# TMS320F28379D.net
KiCad netlist of a schematic drawn in Altium Designer
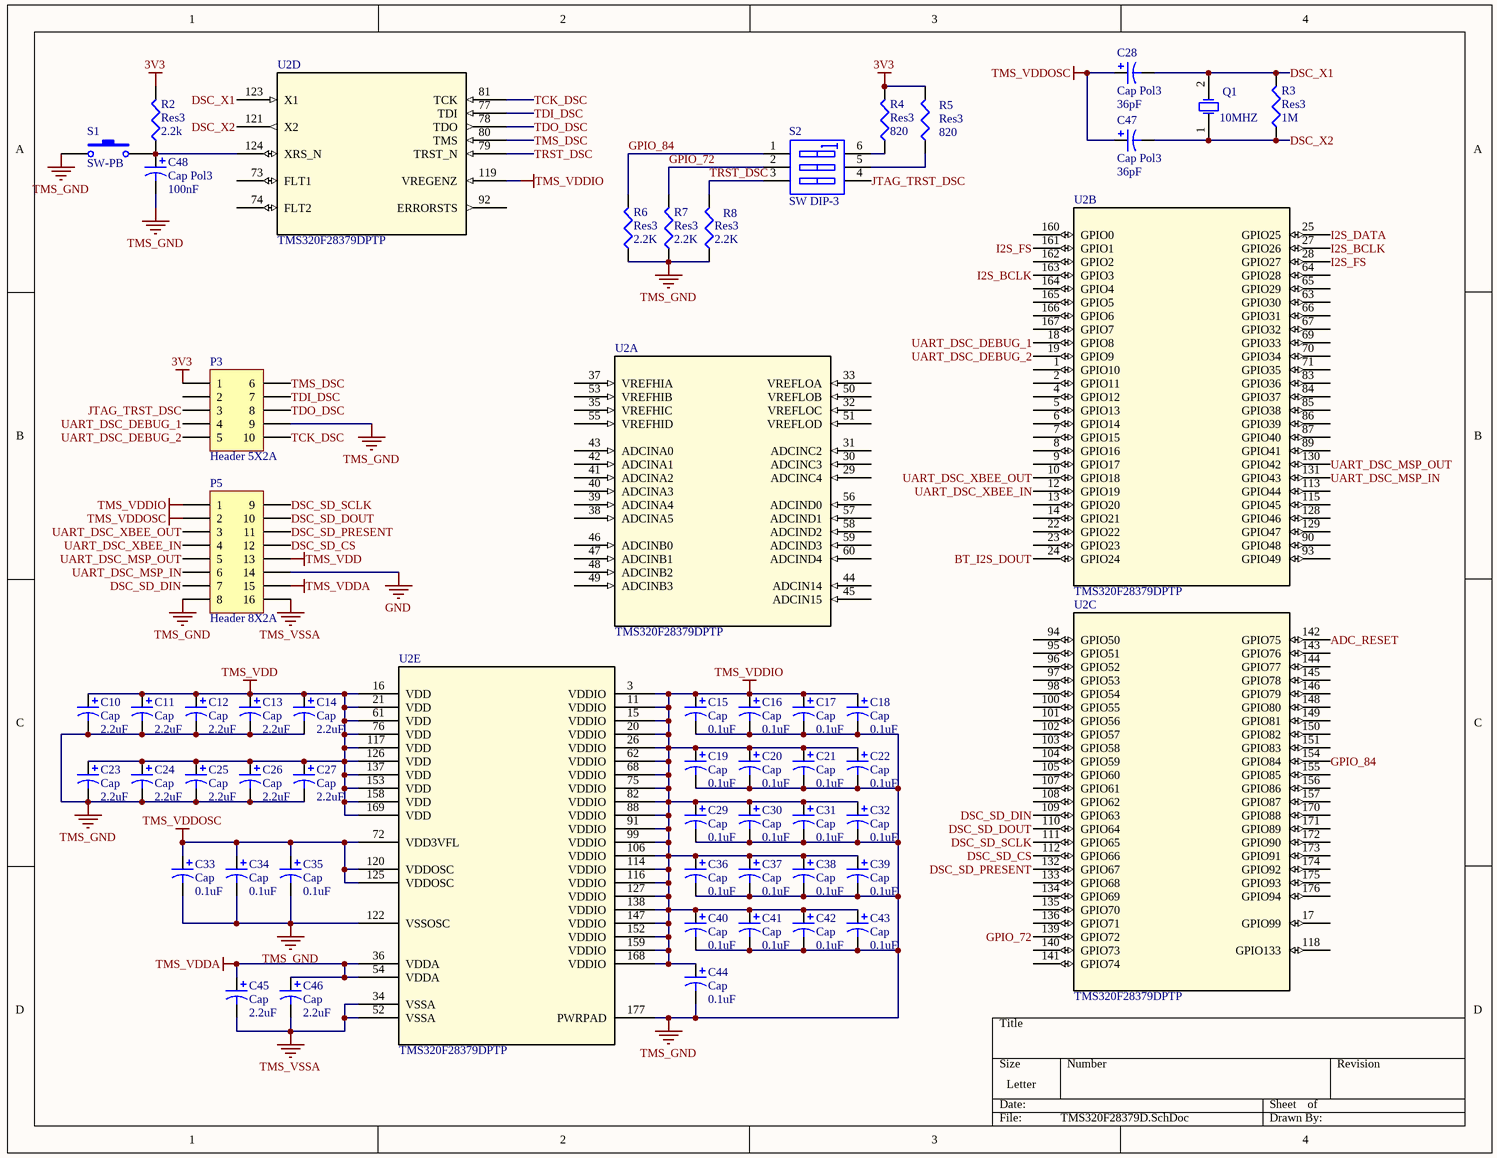
[diagram p0: TMS320F28379D.SchDoc]

(export (version "E")
  (design (tool "Eeschema 10.0.6"))
  (components
    (comp (ref "C10")
      (value "Cap")
      (footprint "C0805")
      (description "Polarized Capacitor (Surface Mount)")
      (fields (field (name "ALTIUM_VALUE") "2.2uF") (field (name "PUBLISHER") "Altium Limited"))
      (libsource (lib "Miscellaneous Devices") (part "Cap Pol3"))
    )
    (comp (ref "C11")
      (value "Cap")
      (footprint "C0805")
      (description "Polarized Capacitor (Surface Mount)")
      (fields (field (name "ALTIUM_VALUE") "2.2uF") (field (name "PUBLISHER") "Altium Limited"))
      (libsource (lib "Miscellaneous Devices") (part "Cap Pol3"))
    )
    (comp (ref "C12")
      (value "Cap")
      (footprint "C0805")
      (description "Polarized Capacitor (Surface Mount)")
      (fields (field (name "ALTIUM_VALUE") "2.2uF") (field (name "PUBLISHER") "Altium Limited"))
      (libsource (lib "Miscellaneous Devices") (part "Cap Pol3"))
    )
    (comp (ref "C13")
      (value "Cap")
      (footprint "C0805")
      (description "Polarized Capacitor (Surface Mount)")
      (fields (field (name "ALTIUM_VALUE") "2.2uF") (field (name "PUBLISHER") "Altium Limited"))
      (libsource (lib "Miscellaneous Devices") (part "Cap Pol3"))
    )
    (comp (ref "C14")
      (value "Cap")
      (footprint "C0805")
      (description "Polarized Capacitor (Surface Mount)")
      (fields (field (name "ALTIUM_VALUE") "2.2uF") (field (name "PUBLISHER") "Altium Limited"))
      (libsource (lib "Miscellaneous Devices") (part "Cap Pol3"))
    )
    (comp (ref "C15")
      (value "Cap")
      (footprint "C0805")
      (description "Polarized Capacitor (Surface Mount)")
      (fields (field (name "ALTIUM_VALUE") "0.1uF") (field (name "PUBLISHER") "Altium Limited"))
      (libsource (lib "Miscellaneous Devices") (part "Cap Pol3"))
    )
    (comp (ref "C16")
      (value "Cap")
      (footprint "C0805")
      (description "Polarized Capacitor (Surface Mount)")
      (fields (field (name "ALTIUM_VALUE") "0.1uF") (field (name "PUBLISHER") "Altium Limited"))
      (libsource (lib "Miscellaneous Devices") (part "Cap Pol3"))
    )
    (comp (ref "C17")
      (value "Cap")
      (footprint "C0805")
      (description "Polarized Capacitor (Surface Mount)")
      (fields (field (name "ALTIUM_VALUE") "0.1uF") (field (name "PUBLISHER") "Altium Limited"))
      (libsource (lib "Miscellaneous Devices") (part "Cap Pol3"))
    )
    (comp (ref "C18")
      (value "Cap")
      (footprint "C0805")
      (description "Polarized Capacitor (Surface Mount)")
      (fields (field (name "ALTIUM_VALUE") "0.1uF") (field (name "PUBLISHER") "Altium Limited"))
      (libsource (lib "Miscellaneous Devices") (part "Cap Pol3"))
    )
    (comp (ref "C19")
      (value "Cap")
      (footprint "C0805")
      (description "Polarized Capacitor (Surface Mount)")
      (fields (field (name "ALTIUM_VALUE") "0.1uF") (field (name "PUBLISHER") "Altium Limited"))
      (libsource (lib "Miscellaneous Devices") (part "Cap Pol3"))
    )
    (comp (ref "C20")
      (value "Cap")
      (footprint "C0805")
      (description "Polarized Capacitor (Surface Mount)")
      (fields (field (name "ALTIUM_VALUE") "0.1uF") (field (name "PUBLISHER") "Altium Limited"))
      (libsource (lib "Miscellaneous Devices") (part "Cap Pol3"))
    )
    (comp (ref "C21")
      (value "Cap")
      (footprint "C0805")
      (description "Polarized Capacitor (Surface Mount)")
      (fields (field (name "ALTIUM_VALUE") "0.1uF") (field (name "PUBLISHER") "Altium Limited"))
      (libsource (lib "Miscellaneous Devices") (part "Cap Pol3"))
    )
    (comp (ref "C22")
      (value "Cap")
      (footprint "C0805")
      (description "Polarized Capacitor (Surface Mount)")
      (fields (field (name "ALTIUM_VALUE") "0.1uF") (field (name "PUBLISHER") "Altium Limited"))
      (libsource (lib "Miscellaneous Devices") (part "Cap Pol3"))
    )
    (comp (ref "C23")
      (value "Cap")
      (footprint "C0805")
      (description "Polarized Capacitor (Surface Mount)")
      (fields (field (name "ALTIUM_VALUE") "2.2uF") (field (name "PUBLISHER") "Altium Limited"))
      (libsource (lib "Miscellaneous Devices") (part "Cap Pol3"))
    )
    (comp (ref "C24")
      (value "Cap")
      (footprint "C0805")
      (description "Polarized Capacitor (Surface Mount)")
      (fields (field (name "ALTIUM_VALUE") "2.2uF") (field (name "PUBLISHER") "Altium Limited"))
      (libsource (lib "Miscellaneous Devices") (part "Cap Pol3"))
    )
    (comp (ref "C25")
      (value "Cap")
      (footprint "C0805")
      (description "Polarized Capacitor (Surface Mount)")
      (fields (field (name "ALTIUM_VALUE") "2.2uF") (field (name "PUBLISHER") "Altium Limited"))
      (libsource (lib "Miscellaneous Devices") (part "Cap Pol3"))
    )
    (comp (ref "C26")
      (value "Cap")
      (footprint "C0805")
      (description "Polarized Capacitor (Surface Mount)")
      (fields (field (name "ALTIUM_VALUE") "2.2uF") (field (name "PUBLISHER") "Altium Limited"))
      (libsource (lib "Miscellaneous Devices") (part "Cap Pol3"))
    )
    (comp (ref "C27")
      (value "Cap")
      (footprint "C0805")
      (description "Polarized Capacitor (Surface Mount)")
      (fields (field (name "ALTIUM_VALUE") "2.2uF") (field (name "PUBLISHER") "Altium Limited"))
      (libsource (lib "Miscellaneous Devices") (part "Cap Pol3"))
    )
    (comp (ref "C28")
      (value "Cap Pol3")
      (footprint "C0805")
      (description "Polarized Capacitor (Surface Mount)")
      (fields (field (name "ALTIUM_VALUE") "36pF") (field (name "PUBLISHER") "Altium Limited"))
      (libsource (lib "Miscellaneous Devices") (part "Cap Pol3"))
    )
    (comp (ref "C29")
      (value "Cap")
      (footprint "C0805")
      (description "Polarized Capacitor (Surface Mount)")
      (fields (field (name "ALTIUM_VALUE") "0.1uF") (field (name "PUBLISHER") "Altium Limited"))
      (libsource (lib "Miscellaneous Devices") (part "Cap Pol3"))
    )
    (comp (ref "C30")
      (value "Cap")
      (footprint "C0805")
      (description "Polarized Capacitor (Surface Mount)")
      (fields (field (name "ALTIUM_VALUE") "0.1uF") (field (name "PUBLISHER") "Altium Limited"))
      (libsource (lib "Miscellaneous Devices") (part "Cap Pol3"))
    )
    (comp (ref "C31")
      (value "Cap")
      (footprint "C0805")
      (description "Polarized Capacitor (Surface Mount)")
      (fields (field (name "ALTIUM_VALUE") "0.1uF") (field (name "PUBLISHER") "Altium Limited"))
      (libsource (lib "Miscellaneous Devices") (part "Cap Pol3"))
    )
    (comp (ref "C32")
      (value "Cap")
      (footprint "C0805")
      (description "Polarized Capacitor (Surface Mount)")
      (fields (field (name "ALTIUM_VALUE") "0.1uF") (field (name "PUBLISHER") "Altium Limited"))
      (libsource (lib "Miscellaneous Devices") (part "Cap Pol3"))
    )
    (comp (ref "C33")
      (value "Cap")
      (footprint "C0805")
      (description "Polarized Capacitor (Surface Mount)")
      (fields (field (name "ALTIUM_VALUE") "0.1uF") (field (name "PUBLISHER") "Altium Limited"))
      (libsource (lib "Miscellaneous Devices") (part "Cap Pol3"))
    )
    (comp (ref "C34")
      (value "Cap")
      (footprint "C0805")
      (description "Polarized Capacitor (Surface Mount)")
      (fields (field (name "ALTIUM_VALUE") "0.1uF") (field (name "PUBLISHER") "Altium Limited"))
      (libsource (lib "Miscellaneous Devices") (part "Cap Pol3"))
    )
    (comp (ref "C35")
      (value "Cap")
      (footprint "C0805")
      (description "Polarized Capacitor (Surface Mount)")
      (fields (field (name "ALTIUM_VALUE") "0.1uF") (field (name "PUBLISHER") "Altium Limited"))
      (libsource (lib "Miscellaneous Devices") (part "Cap Pol3"))
    )
    (comp (ref "C36")
      (value "Cap")
      (footprint "C0805")
      (description "Polarized Capacitor (Surface Mount)")
      (fields (field (name "ALTIUM_VALUE") "0.1uF") (field (name "PUBLISHER") "Altium Limited"))
      (libsource (lib "Miscellaneous Devices") (part "Cap Pol3"))
    )
    (comp (ref "C37")
      (value "Cap")
      (footprint "C0805")
      (description "Polarized Capacitor (Surface Mount)")
      (fields (field (name "ALTIUM_VALUE") "0.1uF") (field (name "PUBLISHER") "Altium Limited"))
      (libsource (lib "Miscellaneous Devices") (part "Cap Pol3"))
    )
    (comp (ref "C38")
      (value "Cap")
      (footprint "C0805")
      (description "Polarized Capacitor (Surface Mount)")
      (fields (field (name "ALTIUM_VALUE") "0.1uF") (field (name "PUBLISHER") "Altium Limited"))
      (libsource (lib "Miscellaneous Devices") (part "Cap Pol3"))
    )
    (comp (ref "C39")
      (value "Cap")
      (footprint "C0805")
      (description "Polarized Capacitor (Surface Mount)")
      (fields (field (name "ALTIUM_VALUE") "0.1uF") (field (name "PUBLISHER") "Altium Limited"))
      (libsource (lib "Miscellaneous Devices") (part "Cap Pol3"))
    )
    (comp (ref "C40")
      (value "Cap")
      (footprint "C0805")
      (description "Polarized Capacitor (Surface Mount)")
      (fields (field (name "ALTIUM_VALUE") "0.1uF") (field (name "PUBLISHER") "Altium Limited"))
      (libsource (lib "Miscellaneous Devices") (part "Cap Pol3"))
    )
    (comp (ref "C41")
      (value "Cap")
      (footprint "C0805")
      (description "Polarized Capacitor (Surface Mount)")
      (fields (field (name "ALTIUM_VALUE") "0.1uF") (field (name "PUBLISHER") "Altium Limited"))
      (libsource (lib "Miscellaneous Devices") (part "Cap Pol3"))
    )
    (comp (ref "C42")
      (value "Cap")
      (footprint "C0805")
      (description "Polarized Capacitor (Surface Mount)")
      (fields (field (name "ALTIUM_VALUE") "0.1uF") (field (name "PUBLISHER") "Altium Limited"))
      (libsource (lib "Miscellaneous Devices") (part "Cap Pol3"))
    )
    (comp (ref "C43")
      (value "Cap")
      (footprint "C0805")
      (description "Polarized Capacitor (Surface Mount)")
      (fields (field (name "ALTIUM_VALUE") "0.1uF") (field (name "PUBLISHER") "Altium Limited"))
      (libsource (lib "Miscellaneous Devices") (part "Cap Pol3"))
    )
    (comp (ref "C44")
      (value "Cap")
      (footprint "C0805")
      (description "Polarized Capacitor (Surface Mount)")
      (fields (field (name "ALTIUM_VALUE") "0.1uF") (field (name "PUBLISHER") "Altium Limited"))
      (libsource (lib "Miscellaneous Devices") (part "Cap Pol3"))
    )
    (comp (ref "C45")
      (value "Cap")
      (footprint "C0805")
      (description "Polarized Capacitor (Surface Mount)")
      (fields (field (name "ALTIUM_VALUE") "2.2uF") (field (name "PUBLISHER") "Altium Limited"))
      (libsource (lib "Miscellaneous Devices") (part "Cap Pol3"))
    )
    (comp (ref "C46")
      (value "Cap")
      (footprint "C0805")
      (description "Polarized Capacitor (Surface Mount)")
      (fields (field (name "ALTIUM_VALUE") "2.2uF") (field (name "PUBLISHER") "Altium Limited"))
      (libsource (lib "Miscellaneous Devices") (part "Cap Pol3"))
    )
    (comp (ref "C47")
      (value "Cap Pol3")
      (footprint "C0805")
      (description "Polarized Capacitor (Surface Mount)")
      (fields (field (name "ALTIUM_VALUE") "36pF") (field (name "PUBLISHER") "Altium Limited"))
      (libsource (lib "Miscellaneous Devices") (part "Cap Pol3"))
    )
    (comp (ref "C48")
      (value "Cap Pol3")
      (footprint "C0805")
      (description "Polarized Capacitor (Surface Mount)")
      (fields (field (name "ALTIUM_VALUE") "100nF") (field (name "PUBLISHER") "Altium Limited"))
      (libsource (lib "Miscellaneous Devices") (part "Cap Pol3"))
    )
    (comp (ref "P3")
      (value "Header 5X2A")
      (footprint "HDR2X5_CEN")
      (description "Header, 5-Pin, Dual row")
      (fields (field (name "PUBLISHER") "Altium Limited"))
      (libsource (lib "Miscellaneous Connectors") (part "Header 5X2A"))
    )
    (comp (ref "P5")
      (value "Header 8X2A")
      (footprint "HDR2X8_CEN")
      (description "Header, 8-Pin, Dual row")
      (fields (field (name "PUBLISHER") "Altium Limited"))
      (libsource (lib "Miscellaneous Connectors") (part "Header 8X2A"))
    )
    (comp (ref "Q1")
      (value "10MHZ")
      (footprint "HC-49U")
      (description "Crystal Oscillator")
      (fields (field (name "PUBLISHER") "Altium Limited"))
      (libsource (lib "ECS Crystal Oscillator") (part "ECS-10-13-1"))
    )
    (comp (ref "R2")
      (value "Res3")
      (footprint "14-1210")
      (description "Resistor")
      (fields (field (name "ALTIUM_VALUE") "2.2k") (field (name "PUBLISHER") "Altium Limited"))
      (libsource (lib "Miscellaneous Devices") (part "Res3"))
    )
    (comp (ref "R3")
      (value "Res3")
      (footprint "14-1210")
      (description "Resistor")
      (fields (field (name "ALTIUM_VALUE") "1M") (field (name "PUBLISHER") "Altium Limited"))
      (libsource (lib "Miscellaneous Devices") (part "Res3"))
    )
    (comp (ref "R4")
      (value "Res3")
      (footprint "14-1210")
      (description "Resistor")
      (fields (field (name "ALTIUM_VALUE") "820") (field (name "PUBLISHER") "Altium Limited"))
      (libsource (lib "Miscellaneous Devices") (part "Res3"))
    )
    (comp (ref "R5")
      (value "Res3")
      (footprint "14-1210")
      (description "Resistor")
      (fields (field (name "ALTIUM_VALUE") "820") (field (name "PUBLISHER") "Altium Limited"))
      (libsource (lib "Miscellaneous Devices") (part "Res3"))
    )
    (comp (ref "R6")
      (value "Res3")
      (footprint "14-1210")
      (description "Resistor")
      (fields (field (name "ALTIUM_VALUE") "2.2K") (field (name "PUBLISHER") "Altium Limited"))
      (libsource (lib "Miscellaneous Devices") (part "Res3"))
    )
    (comp (ref "R7")
      (value "Res3")
      (footprint "14-1210")
      (description "Resistor")
      (fields (field (name "ALTIUM_VALUE") "2.2K") (field (name "PUBLISHER") "Altium Limited"))
      (libsource (lib "Miscellaneous Devices") (part "Res3"))
    )
    (comp (ref "R8")
      (value "Res3")
      (footprint "14-1210")
      (description "Resistor")
      (fields (field (name "ALTIUM_VALUE") "2.2K") (field (name "PUBLISHER") "Altium Limited"))
      (libsource (lib "Miscellaneous Devices") (part "Res3"))
    )
    (comp (ref "S1")
      (value "SW-PB")
      (footprint "SW PB")
      (description "DIGIKEY SW400-ND")
      (fields (field (name "PUBLISHER") "Altium Limited"))
      (libsource (lib "ECE LIB new") (part "SW-PB_2"))
    )
    (comp (ref "S2")
      (value "SW DIP-3")
      (footprint "DIP-6")
      (description "DIP Switch, 3 Position, SPST")
      (fields (field (name "PUBLISHER") "Altium Limited"))
      (libsource (lib "Miscellaneous Devices") (part "SW DIP-3"))
    )
    (comp (ref "U2")
      (value "TMS320F28379DPTP")
      (footprint "PTP0176F_N")
      (description "Imported")
      (fields
        (field (name "PARTNUMBER") "TMS320F28379DPTPS")
        (field (name "MANUFACTURER") "Texas Instruments")
      )
      (libsource (lib "TMS320F28379DPTP") (part "TMS320F28379DPTP"))
    )
  )
  (nets
    (net (code "1") (name "/ADC_RESET") (class "Default")
      (node (ref "U2") (pin "142") (pinfunction "GPIO75_142") (pintype "bidirectional"))
    )
    (net (code "2") (name "/BT_I2S_DOUT") (class "Default")
      (node (ref "U2") (pin "24") (pinfunction "GPIO24_24") (pintype "bidirectional"))
    )
    (net (code "3") (name "/DSC_SD_CS") (class "Default")
      (node (ref "P5") (pin "12") (pinfunction "12_12") (pintype "passive"))
      (node (ref "U2") (pin "112") (pinfunction "GPIO66_112") (pintype "bidirectional"))
    )
    (net (code "4") (name "/DSC_SD_DIN") (class "Default")
      (node (ref "P5") (pin "7") (pinfunction "7_7") (pintype "passive"))
      (node (ref "U2") (pin "109") (pinfunction "GPIO63_109") (pintype "bidirectional"))
    )
    (net (code "5") (name "/DSC_SD_DOUT") (class "Default")
      (node (ref "P5") (pin "10") (pinfunction "10_10") (pintype "passive"))
      (node (ref "U2") (pin "110") (pinfunction "GPIO64_110") (pintype "bidirectional"))
    )
    (net (code "6") (name "/DSC_SD_PRESENT") (class "Default")
      (node (ref "P5") (pin "11") (pinfunction "11_11") (pintype "passive"))
      (node (ref "U2") (pin "132") (pinfunction "GPIO67_132") (pintype "bidirectional"))
    )
    (net (code "7") (name "/DSC_SD_SCLK") (class "Default")
      (node (ref "P5") (pin "9") (pinfunction "9_9") (pintype "passive"))
      (node (ref "U2") (pin "111") (pinfunction "GPIO65_111") (pintype "bidirectional"))
    )
    (net (code "8") (name "/DSC_X1") (class "Default")
      (node (ref "C28") (pin "2") (pinfunction "2_2") (pintype "passive"))
      (node (ref "Q1") (pin "2") (pinfunction "OSC2_2") (pintype "passive"))
      (node (ref "R3") (pin "2") (pinfunction "2_2") (pintype "passive"))
      (node (ref "U2") (pin "123") (pinfunction "X1_123") (pintype "input"))
    )
    (net (code "9") (name "/DSC_X2") (class "Default")
      (node (ref "C47") (pin "2") (pinfunction "2_2") (pintype "passive"))
      (node (ref "Q1") (pin "1") (pinfunction "OSC1_1") (pintype "passive"))
      (node (ref "R3") (pin "1") (pinfunction "1_1") (pintype "passive"))
      (node (ref "U2") (pin "121") (pinfunction "X2_121") (pintype "output"))
    )
    (net (code "10") (name "/GPIO_72") (class "Default")
      (node (ref "R7") (pin "2") (pinfunction "2_2") (pintype "passive"))
      (node (ref "S2") (pin "2") (pinfunction "A2_2") (pintype "passive"))
      (node (ref "U2") (pin "139") (pinfunction "GPIO72_139") (pintype "bidirectional"))
    )
    (net (code "11") (name "/GPIO_84") (class "Default")
      (node (ref "R6") (pin "2") (pinfunction "2_2") (pintype "passive"))
      (node (ref "S2") (pin "1") (pinfunction "A1_1") (pintype "passive"))
      (node (ref "U2") (pin "154") (pinfunction "GPIO84_154") (pintype "bidirectional"))
    )
    (net (code "12") (name "/I2S_BCLK") (class "Default")
      (node (ref "U2") (pin "163") (pinfunction "GPIO3_163") (pintype "bidirectional"))
      (node (ref "U2") (pin "27") (pinfunction "GPIO26_27") (pintype "bidirectional"))
    )
    (net (code "13") (name "/I2S_DATA") (class "Default")
      (node (ref "U2") (pin "25") (pinfunction "GPIO25_25") (pintype "bidirectional"))
    )
    (net (code "14") (name "/I2S_FS") (class "Default")
      (node (ref "U2") (pin "161") (pinfunction "GPIO1_161") (pintype "bidirectional"))
      (node (ref "U2") (pin "28") (pinfunction "GPIO27_28") (pintype "bidirectional"))
    )
    (net (code "15") (name "/JTAG_TRST_DSC") (class "Default")
      (node (ref "P3") (pin "3") (pinfunction "3_3") (pintype "passive"))
      (node (ref "S2") (pin "4") (pinfunction "B3_4") (pintype "passive"))
    )
    (net (code "16") (name "/TCK_DSC") (class "Default")
      (node (ref "P3") (pin "10") (pinfunction "10_10") (pintype "passive"))
      (node (ref "U2") (pin "81") (pinfunction "TCK_81") (pintype "input"))
    )
    (net (code "17") (name "/TDI_DSC") (class "Default")
      (node (ref "P3") (pin "7") (pinfunction "7_7") (pintype "passive"))
      (node (ref "U2") (pin "77") (pinfunction "TDI_77") (pintype "input"))
    )
    (net (code "18") (name "/TDO_DSC") (class "Default")
      (node (ref "P3") (pin "8") (pinfunction "8_8") (pintype "passive"))
      (node (ref "U2") (pin "78") (pinfunction "TDO_78") (pintype "output"))
    )
    (net (code "19") (name "/TMS_DSC") (class "Default")
      (node (ref "P3") (pin "6") (pinfunction "6_6") (pintype "passive"))
      (node (ref "U2") (pin "80") (pinfunction "TMS_80") (pintype "input"))
    )
    (net (code "20") (name "/TRST_DSC") (class "Default")
      (node (ref "R8") (pin "2") (pinfunction "2_2") (pintype "passive"))
      (node (ref "S2") (pin "3") (pinfunction "A3_3") (pintype "passive"))
      (node (ref "U2") (pin "79") (pinfunction "TRST_N_79") (pintype "input"))
    )
    (net (code "21") (name "/UART_DSC_DEBUG_1") (class "Default")
      (node (ref "P3") (pin "4") (pinfunction "4_4") (pintype "passive"))
      (node (ref "U2") (pin "18") (pinfunction "GPIO8_18") (pintype "bidirectional"))
    )
    (net (code "22") (name "/UART_DSC_DEBUG_2") (class "Default")
      (node (ref "P3") (pin "5") (pinfunction "5_5") (pintype "passive"))
      (node (ref "U2") (pin "19") (pinfunction "GPIO9_19") (pintype "bidirectional"))
    )
    (net (code "23") (name "/UART_DSC_MSP_IN") (class "Default")
      (node (ref "P5") (pin "6") (pinfunction "6_6") (pintype "passive"))
      (node (ref "U2") (pin "131") (pinfunction "GPIO43_131") (pintype "bidirectional"))
    )
    (net (code "24") (name "/UART_DSC_MSP_OUT") (class "Default")
      (node (ref "P5") (pin "5") (pinfunction "5_5") (pintype "passive"))
      (node (ref "U2") (pin "130") (pinfunction "GPIO42_130") (pintype "bidirectional"))
    )
    (net (code "25") (name "/UART_DSC_XBEE_IN") (class "Default")
      (node (ref "P5") (pin "4") (pinfunction "4_4") (pintype "passive"))
      (node (ref "U2") (pin "12") (pinfunction "GPIO19_12") (pintype "bidirectional"))
    )
    (net (code "26") (name "/UART_DSC_XBEE_OUT") (class "Default")
      (node (ref "P5") (pin "3") (pinfunction "3_3") (pintype "passive"))
      (node (ref "U2") (pin "10") (pinfunction "GPIO18_10") (pintype "bidirectional"))
    )
    (net (code "27") (name "3V3") (class "Default")
      (node (ref "P3") (pin "1") (pinfunction "1_1") (pintype "passive"))
      (node (ref "R2") (pin "2") (pinfunction "2_2") (pintype "passive"))
      (node (ref "R4") (pin "2") (pinfunction "2_2") (pintype "passive"))
      (node (ref "R5") (pin "2") (pinfunction "2_2") (pintype "passive"))
    )
    (net (code "28") (name "GND") (class "Default")
      (node (ref "P5") (pin "14") (pinfunction "14_14") (pintype "passive"))
    )
    (net (code "29") (name "Net-(S2-B1)") (class "Default")
      (node (ref "R4") (pin "1") (pinfunction "1_1") (pintype "passive"))
      (node (ref "S2") (pin "6") (pinfunction "B1_6") (pintype "passive"))
    )
    (net (code "30") (name "Net-(S2-B2)") (class "Default")
      (node (ref "R5") (pin "1") (pinfunction "1_1") (pintype "passive"))
      (node (ref "S2") (pin "5") (pinfunction "B2_5") (pintype "passive"))
    )
    (net (code "31") (name "Net-(U2D-XRS_N)") (class "Default")
      (node (ref "C48") (pin "1") (pinfunction "1_1") (pintype "passive"))
      (node (ref "R2") (pin "1") (pinfunction "1_1") (pintype "passive"))
      (node (ref "S1") (pin "2") (pinfunction "2_2") (pintype "passive"))
      (node (ref "U2") (pin "124") (pinfunction "XRS_N_124") (pintype "bidirectional"))
    )
    (net (code "32") (name "TMS_GND") (class "Default")
      (node (ref "C10") (pin "2") (pinfunction "2_2") (pintype "passive"))
      (node (ref "C11") (pin "2") (pinfunction "2_2") (pintype "passive"))
      (node (ref "C12") (pin "2") (pinfunction "2_2") (pintype "passive"))
      (node (ref "C13") (pin "2") (pinfunction "2_2") (pintype "passive"))
      (node (ref "C14") (pin "2") (pinfunction "2_2") (pintype "passive"))
      (node (ref "C15") (pin "2") (pinfunction "2_2") (pintype "passive"))
      (node (ref "C16") (pin "2") (pinfunction "2_2") (pintype "passive"))
      (node (ref "C17") (pin "2") (pinfunction "2_2") (pintype "passive"))
      (node (ref "C18") (pin "2") (pinfunction "2_2") (pintype "passive"))
      (node (ref "C19") (pin "2") (pinfunction "2_2") (pintype "passive"))
      (node (ref "C20") (pin "2") (pinfunction "2_2") (pintype "passive"))
      (node (ref "C21") (pin "2") (pinfunction "2_2") (pintype "passive"))
      (node (ref "C22") (pin "2") (pinfunction "2_2") (pintype "passive"))
      (node (ref "C23") (pin "2") (pinfunction "2_2") (pintype "passive"))
      (node (ref "C24") (pin "2") (pinfunction "2_2") (pintype "passive"))
      (node (ref "C25") (pin "2") (pinfunction "2_2") (pintype "passive"))
      (node (ref "C26") (pin "2") (pinfunction "2_2") (pintype "passive"))
      (node (ref "C27") (pin "2") (pinfunction "2_2") (pintype "passive"))
      (node (ref "C29") (pin "2") (pinfunction "2_2") (pintype "passive"))
      (node (ref "C30") (pin "2") (pinfunction "2_2") (pintype "passive"))
      (node (ref "C31") (pin "2") (pinfunction "2_2") (pintype "passive"))
      (node (ref "C32") (pin "2") (pinfunction "2_2") (pintype "passive"))
      (node (ref "C33") (pin "2") (pinfunction "2_2") (pintype "passive"))
      (node (ref "C34") (pin "2") (pinfunction "2_2") (pintype "passive"))
      (node (ref "C35") (pin "2") (pinfunction "2_2") (pintype "passive"))
      (node (ref "C36") (pin "2") (pinfunction "2_2") (pintype "passive"))
      (node (ref "C37") (pin "2") (pinfunction "2_2") (pintype "passive"))
      (node (ref "C38") (pin "2") (pinfunction "2_2") (pintype "passive"))
      (node (ref "C39") (pin "2") (pinfunction "2_2") (pintype "passive"))
      (node (ref "C40") (pin "2") (pinfunction "2_2") (pintype "passive"))
      (node (ref "C41") (pin "2") (pinfunction "2_2") (pintype "passive"))
      (node (ref "C42") (pin "2") (pinfunction "2_2") (pintype "passive"))
      (node (ref "C43") (pin "2") (pinfunction "2_2") (pintype "passive"))
      (node (ref "C44") (pin "2") (pinfunction "2_2") (pintype "passive"))
      (node (ref "C48") (pin "2") (pinfunction "2_2") (pintype "passive"))
      (node (ref "P3") (pin "9") (pinfunction "9_9") (pintype "passive"))
      (node (ref "P5") (pin "8") (pinfunction "8_8") (pintype "passive"))
      (node (ref "R6") (pin "1") (pinfunction "1_1") (pintype "passive"))
      (node (ref "R7") (pin "1") (pinfunction "1_1") (pintype "passive"))
      (node (ref "R8") (pin "1") (pinfunction "1_1") (pintype "passive"))
      (node (ref "S1") (pin "1") (pinfunction "1_1") (pintype "passive"))
      (node (ref "U2") (pin "122") (pinfunction "VSSOSC_122") (pintype "power_in"))
      (node (ref "U2") (pin "177") (pinfunction "PWRPAD_177") (pintype "power_in"))
    )
    (net (code "33") (name "TMS_VDD") (class "Default")
      (node (ref "C10") (pin "1") (pinfunction "1_1") (pintype "passive"))
      (node (ref "C11") (pin "1") (pinfunction "1_1") (pintype "passive"))
      (node (ref "C12") (pin "1") (pinfunction "1_1") (pintype "passive"))
      (node (ref "C13") (pin "1") (pinfunction "1_1") (pintype "passive"))
      (node (ref "C14") (pin "1") (pinfunction "1_1") (pintype "passive"))
      (node (ref "C23") (pin "1") (pinfunction "1_1") (pintype "passive"))
      (node (ref "C24") (pin "1") (pinfunction "1_1") (pintype "passive"))
      (node (ref "C25") (pin "1") (pinfunction "1_1") (pintype "passive"))
      (node (ref "C26") (pin "1") (pinfunction "1_1") (pintype "passive"))
      (node (ref "C27") (pin "1") (pinfunction "1_1") (pintype "passive"))
      (node (ref "P5") (pin "13") (pinfunction "13_13") (pintype "passive"))
      (node (ref "U2") (pin "117") (pinfunction "VDD_117") (pintype "power_in"))
      (node (ref "U2") (pin "126") (pinfunction "VDD_126") (pintype "power_in"))
      (node (ref "U2") (pin "137") (pinfunction "VDD_137") (pintype "power_in"))
      (node (ref "U2") (pin "153") (pinfunction "VDD_153") (pintype "power_in"))
      (node (ref "U2") (pin "158") (pinfunction "VDD_158") (pintype "power_in"))
      (node (ref "U2") (pin "16") (pinfunction "VDD_16") (pintype "power_in"))
      (node (ref "U2") (pin "169") (pinfunction "VDD_169") (pintype "power_in"))
      (node (ref "U2") (pin "21") (pinfunction "VDD_21") (pintype "power_in"))
      (node (ref "U2") (pin "61") (pinfunction "VDD_61") (pintype "power_in"))
      (node (ref "U2") (pin "76") (pinfunction "VDD_76") (pintype "power_in"))
    )
    (net (code "34") (name "TMS_VDDA") (class "Default")
      (node (ref "C45") (pin "1") (pinfunction "1_1") (pintype "passive"))
      (node (ref "C46") (pin "1") (pinfunction "1_1") (pintype "passive"))
      (node (ref "P5") (pin "15") (pinfunction "15_15") (pintype "passive"))
      (node (ref "U2") (pin "36") (pinfunction "VDDA_36") (pintype "power_in"))
      (node (ref "U2") (pin "54") (pinfunction "VDDA_54") (pintype "power_in"))
    )
    (net (code "35") (name "TMS_VDDIO") (class "Default")
      (node (ref "C15") (pin "1") (pinfunction "1_1") (pintype "passive"))
      (node (ref "C16") (pin "1") (pinfunction "1_1") (pintype "passive"))
      (node (ref "C17") (pin "1") (pinfunction "1_1") (pintype "passive"))
      (node (ref "C18") (pin "1") (pinfunction "1_1") (pintype "passive"))
      (node (ref "C19") (pin "1") (pinfunction "1_1") (pintype "passive"))
      (node (ref "C20") (pin "1") (pinfunction "1_1") (pintype "passive"))
      (node (ref "C21") (pin "1") (pinfunction "1_1") (pintype "passive"))
      (node (ref "C22") (pin "1") (pinfunction "1_1") (pintype "passive"))
      (node (ref "C29") (pin "1") (pinfunction "1_1") (pintype "passive"))
      (node (ref "C30") (pin "1") (pinfunction "1_1") (pintype "passive"))
      (node (ref "C31") (pin "1") (pinfunction "1_1") (pintype "passive"))
      (node (ref "C32") (pin "1") (pinfunction "1_1") (pintype "passive"))
      (node (ref "C36") (pin "1") (pinfunction "1_1") (pintype "passive"))
      (node (ref "C37") (pin "1") (pinfunction "1_1") (pintype "passive"))
      (node (ref "C38") (pin "1") (pinfunction "1_1") (pintype "passive"))
      (node (ref "C39") (pin "1") (pinfunction "1_1") (pintype "passive"))
      (node (ref "C40") (pin "1") (pinfunction "1_1") (pintype "passive"))
      (node (ref "C41") (pin "1") (pinfunction "1_1") (pintype "passive"))
      (node (ref "C42") (pin "1") (pinfunction "1_1") (pintype "passive"))
      (node (ref "C43") (pin "1") (pinfunction "1_1") (pintype "passive"))
      (node (ref "C44") (pin "1") (pinfunction "1_1") (pintype "passive"))
      (node (ref "P5") (pin "1") (pinfunction "1_1") (pintype "passive"))
      (node (ref "U2") (pin "106") (pinfunction "VDDIO_106") (pintype "power_in"))
      (node (ref "U2") (pin "11") (pinfunction "VDDIO_11") (pintype "power_in"))
      (node (ref "U2") (pin "114") (pinfunction "VDDIO_114") (pintype "power_in"))
      (node (ref "U2") (pin "116") (pinfunction "VDDIO_116") (pintype "power_in"))
      (node (ref "U2") (pin "119") (pinfunction "VREGENZ_119") (pintype "input"))
      (node (ref "U2") (pin "127") (pinfunction "VDDIO_127") (pintype "power_in"))
      (node (ref "U2") (pin "138") (pinfunction "VDDIO_138") (pintype "power_in"))
      (node (ref "U2") (pin "147") (pinfunction "VDDIO_147") (pintype "power_in"))
      (node (ref "U2") (pin "15") (pinfunction "VDDIO_15") (pintype "power_in"))
      (node (ref "U2") (pin "152") (pinfunction "VDDIO_152") (pintype "power_in"))
      (node (ref "U2") (pin "159") (pinfunction "VDDIO_159") (pintype "power_in"))
      (node (ref "U2") (pin "168") (pinfunction "VDDIO_168") (pintype "power_in"))
      (node (ref "U2") (pin "20") (pinfunction "VDDIO_20") (pintype "power_in"))
      (node (ref "U2") (pin "26") (pinfunction "VDDIO_26") (pintype "power_in"))
      (node (ref "U2") (pin "3") (pinfunction "VDDIO_3") (pintype "power_in"))
      (node (ref "U2") (pin "62") (pinfunction "VDDIO_62") (pintype "power_in"))
      (node (ref "U2") (pin "68") (pinfunction "VDDIO_68") (pintype "power_in"))
      (node (ref "U2") (pin "75") (pinfunction "VDDIO_75") (pintype "power_in"))
      (node (ref "U2") (pin "82") (pinfunction "VDDIO_82") (pintype "power_in"))
      (node (ref "U2") (pin "88") (pinfunction "VDDIO_88") (pintype "power_in"))
      (node (ref "U2") (pin "91") (pinfunction "VDDIO_91") (pintype "power_in"))
      (node (ref "U2") (pin "99") (pinfunction "VDDIO_99") (pintype "power_in"))
    )
    (net (code "36") (name "TMS_VDDOSC") (class "Default")
      (node (ref "C28") (pin "1") (pinfunction "1_1") (pintype "passive"))
      (node (ref "C33") (pin "1") (pinfunction "1_1") (pintype "passive"))
      (node (ref "C34") (pin "1") (pinfunction "1_1") (pintype "passive"))
      (node (ref "C35") (pin "1") (pinfunction "1_1") (pintype "passive"))
      (node (ref "C47") (pin "1") (pinfunction "1_1") (pintype "passive"))
      (node (ref "P5") (pin "2") (pinfunction "2_2") (pintype "passive"))
      (node (ref "U2") (pin "120") (pinfunction "VDDOSC_120") (pintype "power_in"))
      (node (ref "U2") (pin "125") (pinfunction "VDDOSC_125") (pintype "power_in"))
      (node (ref "U2") (pin "72") (pinfunction "VDD3VFL_72") (pintype "power_in"))
    )
    (net (code "37") (name "TMS_VSSA") (class "Default")
      (node (ref "C45") (pin "2") (pinfunction "2_2") (pintype "passive"))
      (node (ref "C46") (pin "2") (pinfunction "2_2") (pintype "passive"))
      (node (ref "P5") (pin "16") (pinfunction "16_16") (pintype "passive"))
      (node (ref "U2") (pin "34") (pinfunction "VSSA_34") (pintype "power_in"))
      (node (ref "U2") (pin "52") (pinfunction "VSSA_52") (pintype "power_in"))
    )
    (net (code "38") (name "unconnected-(P3-Pad2)") (class "Default")
      (node (ref "P3") (pin "2") (pinfunction "2_2") (pintype "passive"))
    )
    (net (code "39") (name "unconnected-(U2A-ADCIN14-Pad44)") (class "Default")
      (node (ref "U2") (pin "44") (pinfunction "ADCIN14_44") (pintype "input"))
    )
    (net (code "40") (name "unconnected-(U2A-ADCIN15-Pad45)") (class "Default")
      (node (ref "U2") (pin "45") (pinfunction "ADCIN15_45") (pintype "input"))
    )
    (net (code "41") (name "unconnected-(U2A-ADCINA0-Pad43)") (class "Default")
      (node (ref "U2") (pin "43") (pinfunction "ADCINA0_43") (pintype "input"))
    )
    (net (code "42") (name "unconnected-(U2A-ADCINA1-Pad42)") (class "Default")
      (node (ref "U2") (pin "42") (pinfunction "ADCINA1_42") (pintype "input"))
    )
    (net (code "43") (name "unconnected-(U2A-ADCINA2-Pad41)") (class "Default")
      (node (ref "U2") (pin "41") (pinfunction "ADCINA2_41") (pintype "input"))
    )
    (net (code "44") (name "unconnected-(U2A-ADCINA3-Pad40)") (class "Default")
      (node (ref "U2") (pin "40") (pinfunction "ADCINA3_40") (pintype "input"))
    )
    (net (code "45") (name "unconnected-(U2A-ADCINA4-Pad39)") (class "Default")
      (node (ref "U2") (pin "39") (pinfunction "ADCINA4_39") (pintype "input"))
    )
    (net (code "46") (name "unconnected-(U2A-ADCINA5-Pad38)") (class "Default")
      (node (ref "U2") (pin "38") (pinfunction "ADCINA5_38") (pintype "input"))
    )
    (net (code "47") (name "unconnected-(U2A-ADCINB0-Pad46)") (class "Default")
      (node (ref "U2") (pin "46") (pinfunction "ADCINB0_46") (pintype "input"))
    )
    (net (code "48") (name "unconnected-(U2A-ADCINB1-Pad47)") (class "Default")
      (node (ref "U2") (pin "47") (pinfunction "ADCINB1_47") (pintype "input"))
    )
    (net (code "49") (name "unconnected-(U2A-ADCINB2-Pad48)") (class "Default")
      (node (ref "U2") (pin "48") (pinfunction "ADCINB2_48") (pintype "input"))
    )
    (net (code "50") (name "unconnected-(U2A-ADCINB3-Pad49)") (class "Default")
      (node (ref "U2") (pin "49") (pinfunction "ADCINB3_49") (pintype "input"))
    )
    (net (code "51") (name "unconnected-(U2A-ADCINC2-Pad31)") (class "Default")
      (node (ref "U2") (pin "31") (pinfunction "ADCINC2_31") (pintype "input"))
    )
    (net (code "52") (name "unconnected-(U2A-ADCINC3-Pad30)") (class "Default")
      (node (ref "U2") (pin "30") (pinfunction "ADCINC3_30") (pintype "input"))
    )
    (net (code "53") (name "unconnected-(U2A-ADCINC4-Pad29)") (class "Default")
      (node (ref "U2") (pin "29") (pinfunction "ADCINC4_29") (pintype "input"))
    )
    (net (code "54") (name "unconnected-(U2A-ADCIND0-Pad56)") (class "Default")
      (node (ref "U2") (pin "56") (pinfunction "ADCIND0_56") (pintype "input"))
    )
    (net (code "55") (name "unconnected-(U2A-ADCIND1-Pad57)") (class "Default")
      (node (ref "U2") (pin "57") (pinfunction "ADCIND1_57") (pintype "input"))
    )
    (net (code "56") (name "unconnected-(U2A-ADCIND2-Pad58)") (class "Default")
      (node (ref "U2") (pin "58") (pinfunction "ADCIND2_58") (pintype "input"))
    )
    (net (code "57") (name "unconnected-(U2A-ADCIND3-Pad59)") (class "Default")
      (node (ref "U2") (pin "59") (pinfunction "ADCIND3_59") (pintype "input"))
    )
    (net (code "58") (name "unconnected-(U2A-ADCIND4-Pad60)") (class "Default")
      (node (ref "U2") (pin "60") (pinfunction "ADCIND4_60") (pintype "input"))
    )
    (net (code "59") (name "unconnected-(U2A-VREFHIA-Pad37)") (class "Default")
      (node (ref "U2") (pin "37") (pinfunction "VREFHIA_37") (pintype "input"))
    )
    (net (code "60") (name "unconnected-(U2A-VREFHIB-Pad53)") (class "Default")
      (node (ref "U2") (pin "53") (pinfunction "VREFHIB_53") (pintype "input"))
    )
    (net (code "61") (name "unconnected-(U2A-VREFHIC-Pad35)") (class "Default")
      (node (ref "U2") (pin "35") (pinfunction "VREFHIC_35") (pintype "input"))
    )
    (net (code "62") (name "unconnected-(U2A-VREFHID-Pad55)") (class "Default")
      (node (ref "U2") (pin "55") (pinfunction "VREFHID_55") (pintype "input"))
    )
    (net (code "63") (name "unconnected-(U2A-VREFLOA-Pad33)") (class "Default")
      (node (ref "U2") (pin "33") (pinfunction "VREFLOA_33") (pintype "input"))
    )
    (net (code "64") (name "unconnected-(U2A-VREFLOB-Pad50)") (class "Default")
      (node (ref "U2") (pin "50") (pinfunction "VREFLOB_50") (pintype "input"))
    )
    (net (code "65") (name "unconnected-(U2A-VREFLOC-Pad32)") (class "Default")
      (node (ref "U2") (pin "32") (pinfunction "VREFLOC_32") (pintype "input"))
    )
    (net (code "66") (name "unconnected-(U2A-VREFLOD-Pad51)") (class "Default")
      (node (ref "U2") (pin "51") (pinfunction "VREFLOD_51") (pintype "input"))
    )
    (net (code "67") (name "unconnected-(U2B-GPIO0-Pad160)") (class "Default")
      (node (ref "U2") (pin "160") (pinfunction "GPIO0_160") (pintype "bidirectional"))
    )
    (net (code "68") (name "unconnected-(U2B-GPIO2-Pad162)") (class "Default")
      (node (ref "U2") (pin "162") (pinfunction "GPIO2_162") (pintype "bidirectional"))
    )
    (net (code "69") (name "unconnected-(U2B-GPIO4-Pad164)") (class "Default")
      (node (ref "U2") (pin "164") (pinfunction "GPIO4_164") (pintype "bidirectional"))
    )
    (net (code "70") (name "unconnected-(U2B-GPIO5-Pad165)") (class "Default")
      (node (ref "U2") (pin "165") (pinfunction "GPIO5_165") (pintype "bidirectional"))
    )
    (net (code "71") (name "unconnected-(U2B-GPIO6-Pad166)") (class "Default")
      (node (ref "U2") (pin "166") (pinfunction "GPIO6_166") (pintype "bidirectional"))
    )
    (net (code "72") (name "unconnected-(U2B-GPIO7-Pad167)") (class "Default")
      (node (ref "U2") (pin "167") (pinfunction "GPIO7_167") (pintype "bidirectional"))
    )
    (net (code "73") (name "unconnected-(U2B-GPIO10-Pad1)") (class "Default")
      (node (ref "U2") (pin "1") (pinfunction "GPIO10_1") (pintype "bidirectional"))
    )
    (net (code "74") (name "unconnected-(U2B-GPIO11-Pad2)") (class "Default")
      (node (ref "U2") (pin "2") (pinfunction "GPIO11_2") (pintype "bidirectional"))
    )
    (net (code "75") (name "unconnected-(U2B-GPIO12-Pad4)") (class "Default")
      (node (ref "U2") (pin "4") (pinfunction "GPIO12_4") (pintype "bidirectional"))
    )
    (net (code "76") (name "unconnected-(U2B-GPIO13-Pad5)") (class "Default")
      (node (ref "U2") (pin "5") (pinfunction "GPIO13_5") (pintype "bidirectional"))
    )
    (net (code "77") (name "unconnected-(U2B-GPIO14-Pad6)") (class "Default")
      (node (ref "U2") (pin "6") (pinfunction "GPIO14_6") (pintype "bidirectional"))
    )
    (net (code "78") (name "unconnected-(U2B-GPIO15-Pad7)") (class "Default")
      (node (ref "U2") (pin "7") (pinfunction "GPIO15_7") (pintype "bidirectional"))
    )
    (net (code "79") (name "unconnected-(U2B-GPIO16-Pad8)") (class "Default")
      (node (ref "U2") (pin "8") (pinfunction "GPIO16_8") (pintype "bidirectional"))
    )
    (net (code "80") (name "unconnected-(U2B-GPIO17-Pad9)") (class "Default")
      (node (ref "U2") (pin "9") (pinfunction "GPIO17_9") (pintype "bidirectional"))
    )
    (net (code "81") (name "unconnected-(U2B-GPIO20-Pad13)") (class "Default")
      (node (ref "U2") (pin "13") (pinfunction "GPIO20_13") (pintype "bidirectional"))
    )
    (net (code "82") (name "unconnected-(U2B-GPIO21-Pad14)") (class "Default")
      (node (ref "U2") (pin "14") (pinfunction "GPIO21_14") (pintype "bidirectional"))
    )
    (net (code "83") (name "unconnected-(U2B-GPIO22-Pad22)") (class "Default")
      (node (ref "U2") (pin "22") (pinfunction "GPIO22_22") (pintype "bidirectional"))
    )
    (net (code "84") (name "unconnected-(U2B-GPIO23-Pad23)") (class "Default")
      (node (ref "U2") (pin "23") (pinfunction "GPIO23_23") (pintype "bidirectional"))
    )
    (net (code "85") (name "unconnected-(U2B-GPIO28-Pad64)") (class "Default")
      (node (ref "U2") (pin "64") (pinfunction "GPIO28_64") (pintype "bidirectional"))
    )
    (net (code "86") (name "unconnected-(U2B-GPIO29-Pad65)") (class "Default")
      (node (ref "U2") (pin "65") (pinfunction "GPIO29_65") (pintype "bidirectional"))
    )
    (net (code "87") (name "unconnected-(U2B-GPIO30-Pad63)") (class "Default")
      (node (ref "U2") (pin "63") (pinfunction "GPIO30_63") (pintype "bidirectional"))
    )
    (net (code "88") (name "unconnected-(U2B-GPIO31-Pad66)") (class "Default")
      (node (ref "U2") (pin "66") (pinfunction "GPIO31_66") (pintype "bidirectional"))
    )
    (net (code "89") (name "unconnected-(U2B-GPIO32-Pad67)") (class "Default")
      (node (ref "U2") (pin "67") (pinfunction "GPIO32_67") (pintype "bidirectional"))
    )
    (net (code "90") (name "unconnected-(U2B-GPIO33-Pad69)") (class "Default")
      (node (ref "U2") (pin "69") (pinfunction "GPIO33_69") (pintype "bidirectional"))
    )
    (net (code "91") (name "unconnected-(U2B-GPIO34-Pad70)") (class "Default")
      (node (ref "U2") (pin "70") (pinfunction "GPIO34_70") (pintype "bidirectional"))
    )
    (net (code "92") (name "unconnected-(U2B-GPIO35-Pad71)") (class "Default")
      (node (ref "U2") (pin "71") (pinfunction "GPIO35_71") (pintype "bidirectional"))
    )
    (net (code "93") (name "unconnected-(U2B-GPIO36-Pad83)") (class "Default")
      (node (ref "U2") (pin "83") (pinfunction "GPIO36_83") (pintype "bidirectional"))
    )
    (net (code "94") (name "unconnected-(U2B-GPIO37-Pad84)") (class "Default")
      (node (ref "U2") (pin "84") (pinfunction "GPIO37_84") (pintype "bidirectional"))
    )
    (net (code "95") (name "unconnected-(U2B-GPIO38-Pad85)") (class "Default")
      (node (ref "U2") (pin "85") (pinfunction "GPIO38_85") (pintype "bidirectional"))
    )
    (net (code "96") (name "unconnected-(U2B-GPIO39-Pad86)") (class "Default")
      (node (ref "U2") (pin "86") (pinfunction "GPIO39_86") (pintype "bidirectional"))
    )
    (net (code "97") (name "unconnected-(U2B-GPIO40-Pad87)") (class "Default")
      (node (ref "U2") (pin "87") (pinfunction "GPIO40_87") (pintype "bidirectional"))
    )
    (net (code "98") (name "unconnected-(U2B-GPIO41-Pad89)") (class "Default")
      (node (ref "U2") (pin "89") (pinfunction "GPIO41_89") (pintype "bidirectional"))
    )
    (net (code "99") (name "unconnected-(U2B-GPIO44-Pad113)") (class "Default")
      (node (ref "U2") (pin "113") (pinfunction "GPIO44_113") (pintype "bidirectional"))
    )
    (net (code "100") (name "unconnected-(U2B-GPIO45-Pad115)") (class "Default")
      (node (ref "U2") (pin "115") (pinfunction "GPIO45_115") (pintype "bidirectional"))
    )
    (net (code "101") (name "unconnected-(U2B-GPIO46-Pad128)") (class "Default")
      (node (ref "U2") (pin "128") (pinfunction "GPIO46_128") (pintype "bidirectional"))
    )
    (net (code "102") (name "unconnected-(U2B-GPIO47-Pad129)") (class "Default")
      (node (ref "U2") (pin "129") (pinfunction "GPIO47_129") (pintype "bidirectional"))
    )
    (net (code "103") (name "unconnected-(U2B-GPIO48-Pad90)") (class "Default")
      (node (ref "U2") (pin "90") (pinfunction "GPIO48_90") (pintype "bidirectional"))
    )
    (net (code "104") (name "unconnected-(U2B-GPIO49-Pad93)") (class "Default")
      (node (ref "U2") (pin "93") (pinfunction "GPIO49_93") (pintype "bidirectional"))
    )
    (net (code "105") (name "unconnected-(U2C-GPIO50-Pad94)") (class "Default")
      (node (ref "U2") (pin "94") (pinfunction "GPIO50_94") (pintype "bidirectional"))
    )
    (net (code "106") (name "unconnected-(U2C-GPIO51-Pad95)") (class "Default")
      (node (ref "U2") (pin "95") (pinfunction "GPIO51_95") (pintype "bidirectional"))
    )
    (net (code "107") (name "unconnected-(U2C-GPIO52-Pad96)") (class "Default")
      (node (ref "U2") (pin "96") (pinfunction "GPIO52_96") (pintype "bidirectional"))
    )
    (net (code "108") (name "unconnected-(U2C-GPIO53-Pad97)") (class "Default")
      (node (ref "U2") (pin "97") (pinfunction "GPIO53_97") (pintype "bidirectional"))
    )
    (net (code "109") (name "unconnected-(U2C-GPIO54-Pad98)") (class "Default")
      (node (ref "U2") (pin "98") (pinfunction "GPIO54_98") (pintype "bidirectional"))
    )
    (net (code "110") (name "unconnected-(U2C-GPIO55-Pad100)") (class "Default")
      (node (ref "U2") (pin "100") (pinfunction "GPIO55_100") (pintype "bidirectional"))
    )
    (net (code "111") (name "unconnected-(U2C-GPIO56-Pad101)") (class "Default")
      (node (ref "U2") (pin "101") (pinfunction "GPIO56_101") (pintype "bidirectional"))
    )
    (net (code "112") (name "unconnected-(U2C-GPIO57-Pad102)") (class "Default")
      (node (ref "U2") (pin "102") (pinfunction "GPIO57_102") (pintype "bidirectional"))
    )
    (net (code "113") (name "unconnected-(U2C-GPIO58-Pad103)") (class "Default")
      (node (ref "U2") (pin "103") (pinfunction "GPIO58_103") (pintype "bidirectional"))
    )
    (net (code "114") (name "unconnected-(U2C-GPIO59-Pad104)") (class "Default")
      (node (ref "U2") (pin "104") (pinfunction "GPIO59_104") (pintype "bidirectional"))
    )
    (net (code "115") (name "unconnected-(U2C-GPIO60-Pad105)") (class "Default")
      (node (ref "U2") (pin "105") (pinfunction "GPIO60_105") (pintype "bidirectional"))
    )
    (net (code "116") (name "unconnected-(U2C-GPIO61-Pad107)") (class "Default")
      (node (ref "U2") (pin "107") (pinfunction "GPIO61_107") (pintype "bidirectional"))
    )
    (net (code "117") (name "unconnected-(U2C-GPIO62-Pad108)") (class "Default")
      (node (ref "U2") (pin "108") (pinfunction "GPIO62_108") (pintype "bidirectional"))
    )
    (net (code "118") (name "unconnected-(U2C-GPIO68-Pad133)") (class "Default")
      (node (ref "U2") (pin "133") (pinfunction "GPIO68_133") (pintype "bidirectional"))
    )
    (net (code "119") (name "unconnected-(U2C-GPIO69-Pad134)") (class "Default")
      (node (ref "U2") (pin "134") (pinfunction "GPIO69_134") (pintype "bidirectional"))
    )
    (net (code "120") (name "unconnected-(U2C-GPIO70-Pad135)") (class "Default")
      (node (ref "U2") (pin "135") (pinfunction "GPIO70_135") (pintype "bidirectional"))
    )
    (net (code "121") (name "unconnected-(U2C-GPIO71-Pad136)") (class "Default")
      (node (ref "U2") (pin "136") (pinfunction "GPIO71_136") (pintype "bidirectional"))
    )
    (net (code "122") (name "unconnected-(U2C-GPIO73-Pad140)") (class "Default")
      (node (ref "U2") (pin "140") (pinfunction "GPIO73_140") (pintype "bidirectional"))
    )
    (net (code "123") (name "unconnected-(U2C-GPIO74-Pad141)") (class "Default")
      (node (ref "U2") (pin "141") (pinfunction "GPIO74_141") (pintype "bidirectional"))
    )
    (net (code "124") (name "unconnected-(U2C-GPIO76-Pad143)") (class "Default")
      (node (ref "U2") (pin "143") (pinfunction "GPIO76_143") (pintype "bidirectional"))
    )
    (net (code "125") (name "unconnected-(U2C-GPIO77-Pad144)") (class "Default")
      (node (ref "U2") (pin "144") (pinfunction "GPIO77_144") (pintype "bidirectional"))
    )
    (net (code "126") (name "unconnected-(U2C-GPIO78-Pad145)") (class "Default")
      (node (ref "U2") (pin "145") (pinfunction "GPIO78_145") (pintype "bidirectional"))
    )
    (net (code "127") (name "unconnected-(U2C-GPIO79-Pad146)") (class "Default")
      (node (ref "U2") (pin "146") (pinfunction "GPIO79_146") (pintype "bidirectional"))
    )
    (net (code "128") (name "unconnected-(U2C-GPIO80-Pad148)") (class "Default")
      (node (ref "U2") (pin "148") (pinfunction "GPIO80_148") (pintype "bidirectional"))
    )
    (net (code "129") (name "unconnected-(U2C-GPIO81-Pad149)") (class "Default")
      (node (ref "U2") (pin "149") (pinfunction "GPIO81_149") (pintype "bidirectional"))
    )
    (net (code "130") (name "unconnected-(U2C-GPIO82-Pad150)") (class "Default")
      (node (ref "U2") (pin "150") (pinfunction "GPIO82_150") (pintype "bidirectional"))
    )
    (net (code "131") (name "unconnected-(U2C-GPIO83-Pad151)") (class "Default")
      (node (ref "U2") (pin "151") (pinfunction "GPIO83_151") (pintype "bidirectional"))
    )
    (net (code "132") (name "unconnected-(U2C-GPIO85-Pad155)") (class "Default")
      (node (ref "U2") (pin "155") (pinfunction "GPIO85_155") (pintype "bidirectional"))
    )
    (net (code "133") (name "unconnected-(U2C-GPIO86-Pad156)") (class "Default")
      (node (ref "U2") (pin "156") (pinfunction "GPIO86_156") (pintype "bidirectional"))
    )
    (net (code "134") (name "unconnected-(U2C-GPIO87-Pad157)") (class "Default")
      (node (ref "U2") (pin "157") (pinfunction "GPIO87_157") (pintype "bidirectional"))
    )
    (net (code "135") (name "unconnected-(U2C-GPIO88-Pad170)") (class "Default")
      (node (ref "U2") (pin "170") (pinfunction "GPIO88_170") (pintype "bidirectional"))
    )
    (net (code "136") (name "unconnected-(U2C-GPIO89-Pad171)") (class "Default")
      (node (ref "U2") (pin "171") (pinfunction "GPIO89_171") (pintype "bidirectional"))
    )
    (net (code "137") (name "unconnected-(U2C-GPIO90-Pad172)") (class "Default")
      (node (ref "U2") (pin "172") (pinfunction "GPIO90_172") (pintype "bidirectional"))
    )
    (net (code "138") (name "unconnected-(U2C-GPIO91-Pad173)") (class "Default")
      (node (ref "U2") (pin "173") (pinfunction "GPIO91_173") (pintype "bidirectional"))
    )
    (net (code "139") (name "unconnected-(U2C-GPIO92-Pad174)") (class "Default")
      (node (ref "U2") (pin "174") (pinfunction "GPIO92_174") (pintype "bidirectional"))
    )
    (net (code "140") (name "unconnected-(U2C-GPIO93-Pad175)") (class "Default")
      (node (ref "U2") (pin "175") (pinfunction "GPIO93_175") (pintype "bidirectional"))
    )
    (net (code "141") (name "unconnected-(U2C-GPIO94-Pad176)") (class "Default")
      (node (ref "U2") (pin "176") (pinfunction "GPIO94_176") (pintype "bidirectional"))
    )
    (net (code "142") (name "unconnected-(U2C-GPIO99-Pad17)") (class "Default")
      (node (ref "U2") (pin "17") (pinfunction "GPIO99_17") (pintype "bidirectional"))
    )
    (net (code "143") (name "unconnected-(U2C-GPIO133-Pad118)") (class "Default")
      (node (ref "U2") (pin "118") (pinfunction "GPIO133_118") (pintype "bidirectional"))
    )
    (net (code "144") (name "unconnected-(U2D-ERRORSTS-Pad92)") (class "Default")
      (node (ref "U2") (pin "92") (pinfunction "ERRORSTS_92") (pintype "output"))
    )
    (net (code "145") (name "unconnected-(U2D-FLT1-Pad73)") (class "Default")
      (node (ref "U2") (pin "73") (pinfunction "FLT1_73") (pintype "bidirectional"))
    )
    (net (code "146") (name "unconnected-(U2D-FLT2-Pad74)") (class "Default")
      (node (ref "U2") (pin "74") (pinfunction "FLT2_74") (pintype "bidirectional"))
    )
  )
)
